# Ilumitunes-IR-String-Controller-v11.net
KiCad netlist of a schematic drawn in EAGLE
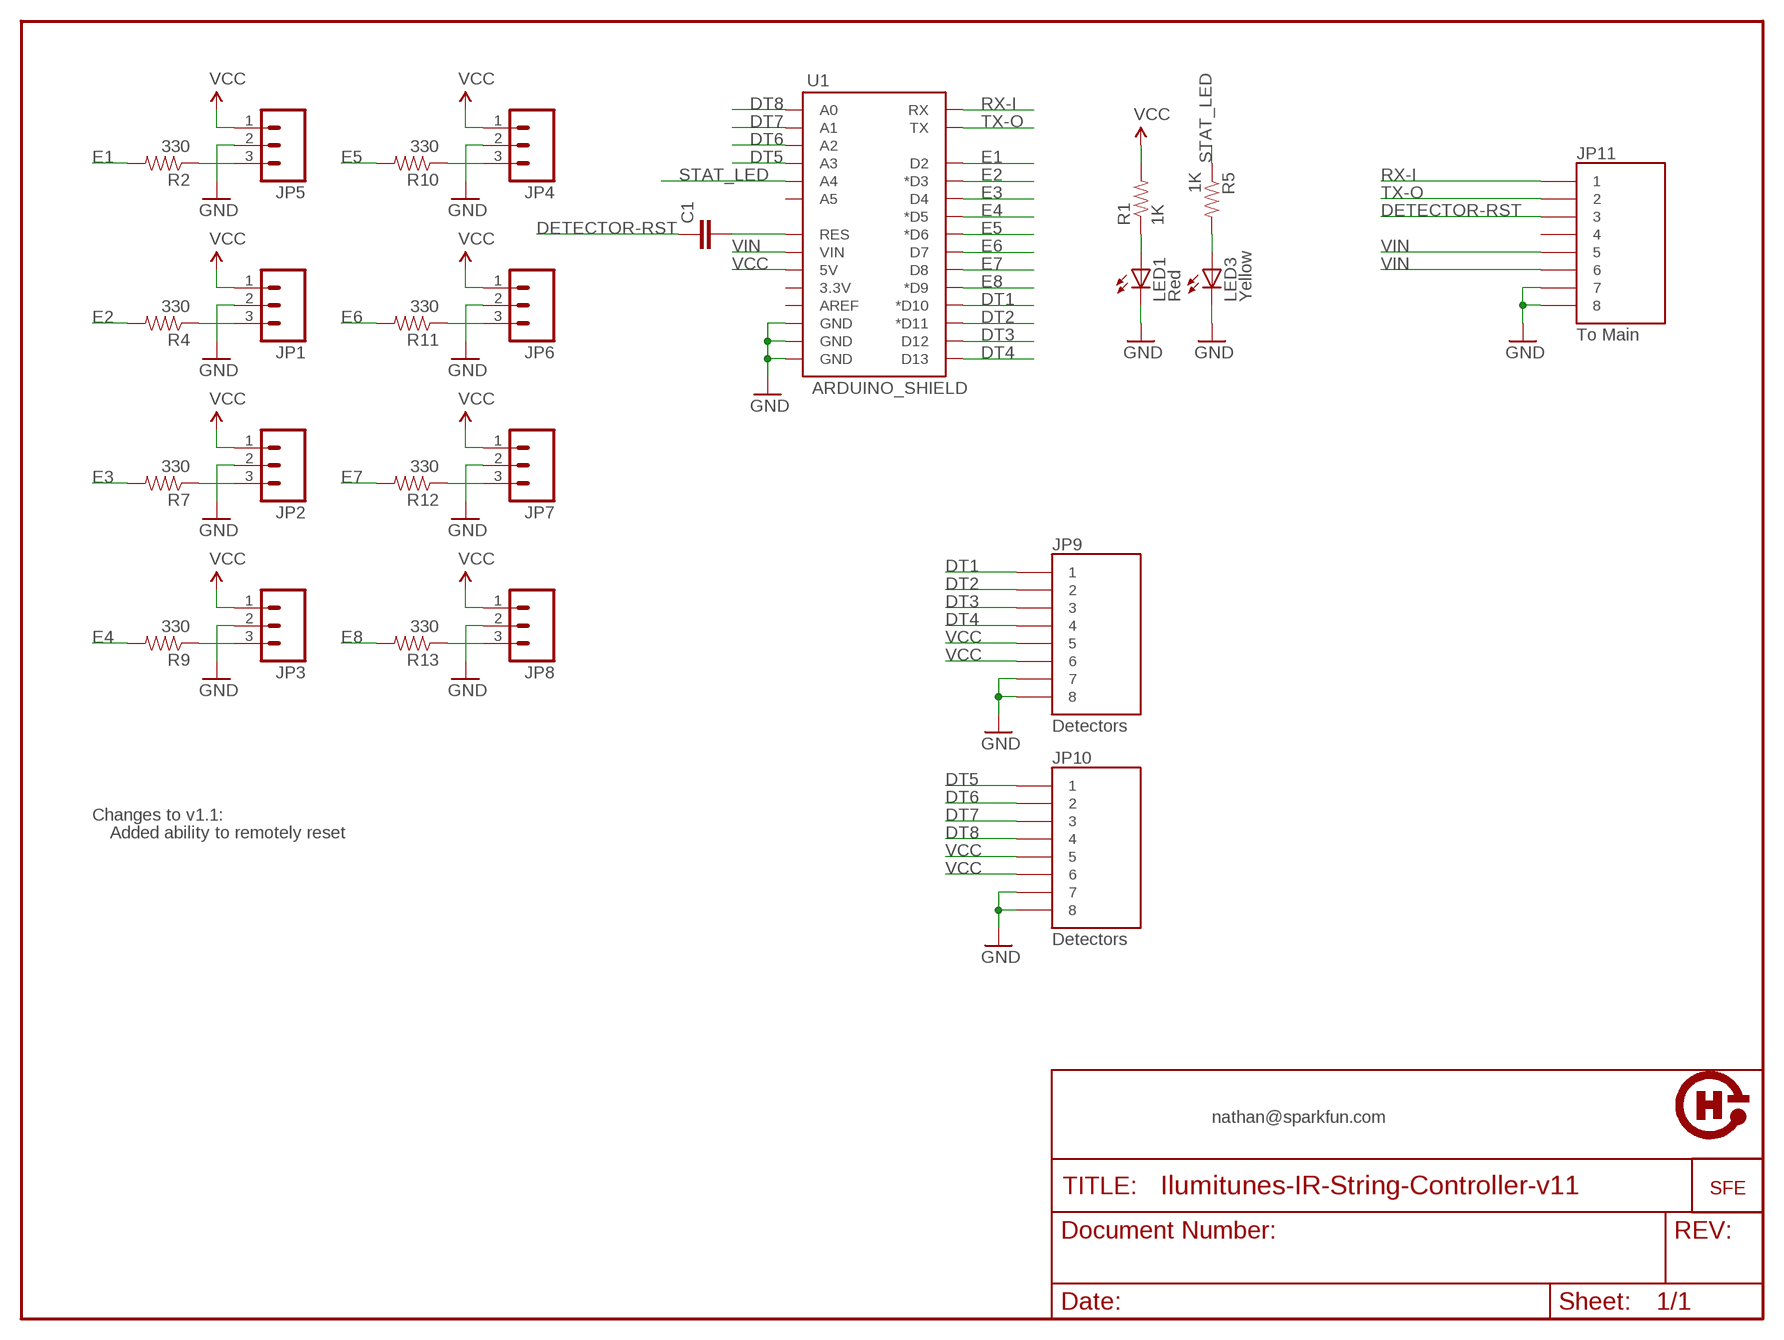
[diagram p0: schematic, sheet 1]

(export (version "E")
  (design (tool "Eeschema 10.0.6"))
  (components
    (comp (ref "C1")
      (value "CAPPTH2")
      (footprint "eagle-import:CAP-PTH-SMALL2")
      (libsource (lib "eagle-import") (part "CAPPTH2"))
    )
    (comp (ref "JP1")
      (value "M03JST-PTH-VERT")
      (footprint "eagle-import:JST-3-PTH-VERT")
      (libsource (lib "eagle-import") (part "M03JST-PTH-VERT"))
    )
    (comp (ref "JP2")
      (value "M03JST-PTH-VERT")
      (footprint "eagle-import:JST-3-PTH-VERT")
      (libsource (lib "eagle-import") (part "M03JST-PTH-VERT"))
    )
    (comp (ref "JP3")
      (value "M03JST-PTH-VERT")
      (footprint "eagle-import:JST-3-PTH-VERT")
      (libsource (lib "eagle-import") (part "M03JST-PTH-VERT"))
    )
    (comp (ref "JP4")
      (value "M03JST-PTH-VERT")
      (footprint "eagle-import:JST-3-PTH-VERT")
      (libsource (lib "eagle-import") (part "M03JST-PTH-VERT"))
    )
    (comp (ref "JP5")
      (value "M03JST-PTH-VERT")
      (footprint "eagle-import:JST-3-PTH-VERT")
      (libsource (lib "eagle-import") (part "M03JST-PTH-VERT"))
    )
    (comp (ref "JP6")
      (value "M03JST-PTH-VERT")
      (footprint "eagle-import:JST-3-PTH-VERT")
      (libsource (lib "eagle-import") (part "M03JST-PTH-VERT"))
    )
    (comp (ref "JP7")
      (value "M03JST-PTH-VERT")
      (footprint "eagle-import:JST-3-PTH-VERT")
      (libsource (lib "eagle-import") (part "M03JST-PTH-VERT"))
    )
    (comp (ref "JP8")
      (value "M03JST-PTH-VERT")
      (footprint "eagle-import:JST-3-PTH-VERT")
      (libsource (lib "eagle-import") (part "M03JST-PTH-VERT"))
    )
    (comp (ref "JP9")
      (value "Detectors")
      (footprint "eagle-import:RJ45-8")
      (libsource (lib "eagle-import") (part "RJ45-8PTH"))
    )
    (comp (ref "JP10")
      (value "Detectors")
      (footprint "eagle-import:RJ45-8")
      (libsource (lib "eagle-import") (part "RJ45-8PTH"))
    )
    (comp (ref "JP11")
      (value "To Main")
      (footprint "eagle-import:RJ45-8")
      (libsource (lib "eagle-import") (part "RJ45-8PTH"))
    )
    (comp (ref "LED1")
      (value "Red")
      (footprint "eagle-import:LED5MM")
      (libsource (lib "eagle-import") (part "LED5MM"))
    )
    (comp (ref "LED3")
      (value "Yellow")
      (footprint "eagle-import:LED5MM")
      (libsource (lib "eagle-import") (part "LED5MM"))
    )
    (comp (ref "R1")
      (value "1K")
      (footprint "eagle-import:AXIAL-0.3")
      (libsource (lib "eagle-import") (part "RESISTORAXIAL-0.3"))
    )
    (comp (ref "R2")
      (value "330")
      (footprint "eagle-import:AXIAL-0.3")
      (libsource (lib "eagle-import") (part "RESISTORAXIAL-0.3"))
    )
    (comp (ref "R4")
      (value "330")
      (footprint "eagle-import:AXIAL-0.3")
      (libsource (lib "eagle-import") (part "RESISTORAXIAL-0.3"))
    )
    (comp (ref "R5")
      (value "1K")
      (footprint "eagle-import:AXIAL-0.3")
      (libsource (lib "eagle-import") (part "RESISTORAXIAL-0.3"))
    )
    (comp (ref "R7")
      (value "330")
      (footprint "eagle-import:AXIAL-0.3")
      (libsource (lib "eagle-import") (part "RESISTORAXIAL-0.3"))
    )
    (comp (ref "R9")
      (value "330")
      (footprint "eagle-import:AXIAL-0.3")
      (libsource (lib "eagle-import") (part "RESISTORAXIAL-0.3"))
    )
    (comp (ref "R10")
      (value "330")
      (footprint "eagle-import:AXIAL-0.3")
      (libsource (lib "eagle-import") (part "RESISTORAXIAL-0.3"))
    )
    (comp (ref "R11")
      (value "330")
      (footprint "eagle-import:AXIAL-0.3")
      (libsource (lib "eagle-import") (part "RESISTORAXIAL-0.3"))
    )
    (comp (ref "R12")
      (value "330")
      (footprint "eagle-import:AXIAL-0.3")
      (libsource (lib "eagle-import") (part "RESISTORAXIAL-0.3"))
    )
    (comp (ref "R13")
      (value "330")
      (footprint "eagle-import:AXIAL-0.3")
      (libsource (lib "eagle-import") (part "RESISTORAXIAL-0.3"))
    )
    (comp (ref "U$1")
      (value "LOGO-SFENEW")
      (footprint "eagle-import:SFE-NEW-WEBLOGO")
      (libsource (lib "eagle-import") (part "LOGO-SFENEW"))
    )
    (comp (ref "U$2")
      (value "OSHW-LOGO")
      (footprint "eagle-import:OSHW-LOGO")
      (libsource (lib "eagle-import") (part "OSHW-LOGO"))
    )
    (comp (ref "U1")
      (value "ARDUINO_SHIELD")
      (footprint "eagle-import:DUEMILANOVE_SHIELD")
      (libsource (lib "eagle-import") (part "ARDUINO_SHIELDLABEL"))
    )
  )
  (nets
    (net (code "1") (name "/DETECTOR-RST") (class "Default")
      (node (ref "C1") (pin "1") (pinfunction "1_1") (pintype "passive"))
      (node (ref "JP11") (pin "3") (pinfunction "3_3") (pintype "bidirectional"))
    )
    (net (code "2") (name "/DT1") (class "Default")
      (node (ref "JP9") (pin "1") (pinfunction "1_1") (pintype "bidirectional"))
      (node (ref "U1") (pin "D10") (pinfunction "*D10_D10") (pintype "bidirectional"))
    )
    (net (code "3") (name "/DT2") (class "Default")
      (node (ref "JP9") (pin "2") (pinfunction "2_2") (pintype "bidirectional"))
      (node (ref "U1") (pin "D11") (pinfunction "*D11_D11") (pintype "bidirectional"))
    )
    (net (code "4") (name "/DT3") (class "Default")
      (node (ref "JP9") (pin "3") (pinfunction "3_3") (pintype "bidirectional"))
      (node (ref "U1") (pin "D12") (pinfunction "D12_D12") (pintype "bidirectional"))
    )
    (net (code "5") (name "/DT4") (class "Default")
      (node (ref "JP9") (pin "4") (pinfunction "4_4") (pintype "bidirectional"))
      (node (ref "U1") (pin "D13") (pinfunction "D13_D13") (pintype "bidirectional"))
    )
    (net (code "6") (name "/DT5") (class "Default")
      (node (ref "JP10") (pin "1") (pinfunction "1_1") (pintype "bidirectional"))
      (node (ref "U1") (pin "A3") (pinfunction "A3_A3") (pintype "bidirectional"))
    )
    (net (code "7") (name "/DT6") (class "Default")
      (node (ref "JP10") (pin "2") (pinfunction "2_2") (pintype "bidirectional"))
      (node (ref "U1") (pin "A2") (pinfunction "A2_A2") (pintype "bidirectional"))
    )
    (net (code "8") (name "/DT7") (class "Default")
      (node (ref "JP10") (pin "3") (pinfunction "3_3") (pintype "bidirectional"))
      (node (ref "U1") (pin "A1") (pinfunction "A1_A1") (pintype "bidirectional"))
    )
    (net (code "9") (name "/DT8") (class "Default")
      (node (ref "JP10") (pin "4") (pinfunction "4_4") (pintype "bidirectional"))
      (node (ref "U1") (pin "A0") (pinfunction "A0_A0") (pintype "bidirectional"))
    )
    (net (code "10") (name "/E1") (class "Default")
      (node (ref "R2") (pin "P$2") (pinfunction "2_P$2") (pintype "passive"))
      (node (ref "U1") (pin "D2") (pinfunction "D2_D2") (pintype "bidirectional"))
    )
    (net (code "11") (name "/E2") (class "Default")
      (node (ref "R4") (pin "P$2") (pinfunction "2_P$2") (pintype "passive"))
      (node (ref "U1") (pin "D3") (pinfunction "*D3_D3") (pintype "bidirectional"))
    )
    (net (code "12") (name "/E3") (class "Default")
      (node (ref "R7") (pin "P$2") (pinfunction "2_P$2") (pintype "passive"))
      (node (ref "U1") (pin "D4") (pinfunction "D4_D4") (pintype "bidirectional"))
    )
    (net (code "13") (name "/E4") (class "Default")
      (node (ref "R9") (pin "P$2") (pinfunction "2_P$2") (pintype "passive"))
      (node (ref "U1") (pin "D5") (pinfunction "*D5_D5") (pintype "bidirectional"))
    )
    (net (code "14") (name "/E5") (class "Default")
      (node (ref "R10") (pin "P$2") (pinfunction "2_P$2") (pintype "passive"))
      (node (ref "U1") (pin "D6") (pinfunction "*D6_D6") (pintype "bidirectional"))
    )
    (net (code "15") (name "/E6") (class "Default")
      (node (ref "R11") (pin "P$2") (pinfunction "2_P$2") (pintype "passive"))
      (node (ref "U1") (pin "D7") (pinfunction "D7_D7") (pintype "bidirectional"))
    )
    (net (code "16") (name "/E7") (class "Default")
      (node (ref "R12") (pin "P$2") (pinfunction "2_P$2") (pintype "passive"))
      (node (ref "U1") (pin "D8") (pinfunction "D8_D8") (pintype "bidirectional"))
    )
    (net (code "17") (name "/E8") (class "Default")
      (node (ref "R13") (pin "P$2") (pinfunction "2_P$2") (pintype "passive"))
      (node (ref "U1") (pin "D9") (pinfunction "*D9_D9") (pintype "bidirectional"))
    )
    (net (code "18") (name "/RX-I") (class "Default")
      (node (ref "JP11") (pin "1") (pinfunction "1_1") (pintype "bidirectional"))
      (node (ref "U1") (pin "RX") (pinfunction "RX_RX") (pintype "bidirectional"))
    )
    (net (code "19") (name "/STAT_LED") (class "Default")
      (node (ref "R5") (pin "P$1") (pinfunction "1_P$1") (pintype "passive"))
      (node (ref "U1") (pin "A4") (pinfunction "A4_A4") (pintype "bidirectional"))
    )
    (net (code "20") (name "/TX-O") (class "Default")
      (node (ref "JP11") (pin "2") (pinfunction "2_2") (pintype "bidirectional"))
      (node (ref "U1") (pin "TX") (pinfunction "TX_TX") (pintype "bidirectional"))
    )
    (net (code "21") (name "/VIN") (class "Default")
      (node (ref "JP11") (pin "5") (pinfunction "5_5") (pintype "bidirectional"))
      (node (ref "JP11") (pin "6") (pinfunction "6_6") (pintype "bidirectional"))
      (node (ref "U1") (pin "VIN") (pinfunction "VIN_VIN") (pintype "bidirectional"))
    )
    (net (code "22") (name "GND") (class "Default")
      (node (ref "JP1") (pin "2") (pinfunction "2_2") (pintype "passive"))
      (node (ref "JP10") (pin "7") (pinfunction "7_7") (pintype "bidirectional"))
      (node (ref "JP10") (pin "8") (pinfunction "8_8") (pintype "bidirectional"))
      (node (ref "JP11") (pin "7") (pinfunction "7_7") (pintype "bidirectional"))
      (node (ref "JP11") (pin "8") (pinfunction "8_8") (pintype "bidirectional"))
      (node (ref "JP2") (pin "2") (pinfunction "2_2") (pintype "passive"))
      (node (ref "JP3") (pin "2") (pinfunction "2_2") (pintype "passive"))
      (node (ref "JP4") (pin "2") (pinfunction "2_2") (pintype "passive"))
      (node (ref "JP5") (pin "2") (pinfunction "2_2") (pintype "passive"))
      (node (ref "JP6") (pin "2") (pinfunction "2_2") (pintype "passive"))
      (node (ref "JP7") (pin "2") (pinfunction "2_2") (pintype "passive"))
      (node (ref "JP8") (pin "2") (pinfunction "2_2") (pintype "passive"))
      (node (ref "JP9") (pin "7") (pinfunction "7_7") (pintype "bidirectional"))
      (node (ref "JP9") (pin "8") (pinfunction "8_8") (pintype "bidirectional"))
      (node (ref "LED1") (pin "K") (pinfunction "C_K") (pintype "passive"))
      (node (ref "LED3") (pin "K") (pinfunction "C_K") (pintype "passive"))
      (node (ref "U1") (pin "GND@0") (pinfunction "GND_GND@0") (pintype "bidirectional"))
      (node (ref "U1") (pin "GND@1") (pinfunction "GND_GND@1") (pintype "bidirectional"))
      (node (ref "U1") (pin "GND@2") (pinfunction "GND_GND@2") (pintype "bidirectional"))
    )
    (net (code "23") (name "Net-(C1-Pad2)") (class "Default")
      (node (ref "C1") (pin "2") (pinfunction "2_2") (pintype "passive"))
      (node (ref "U1") (pin "RES") (pinfunction "RES_RES") (pintype "bidirectional"))
    )
    (net (code "24") (name "Net-(R1-1)") (class "Default")
      (node (ref "LED1") (pin "A") (pinfunction "A_A") (pintype "passive"))
      (node (ref "R1") (pin "P$1") (pinfunction "1_P$1") (pintype "passive"))
    )
    (net (code "25") (name "Net-(R2-1)") (class "Default")
      (node (ref "JP5") (pin "3") (pinfunction "3_3") (pintype "passive"))
      (node (ref "R2") (pin "P$1") (pinfunction "1_P$1") (pintype "passive"))
    )
    (net (code "26") (name "Net-(R4-1)") (class "Default")
      (node (ref "JP1") (pin "3") (pinfunction "3_3") (pintype "passive"))
      (node (ref "R4") (pin "P$1") (pinfunction "1_P$1") (pintype "passive"))
    )
    (net (code "27") (name "Net-(R5-2)") (class "Default")
      (node (ref "LED3") (pin "A") (pinfunction "A_A") (pintype "passive"))
      (node (ref "R5") (pin "P$2") (pinfunction "2_P$2") (pintype "passive"))
    )
    (net (code "28") (name "Net-(R7-1)") (class "Default")
      (node (ref "JP2") (pin "3") (pinfunction "3_3") (pintype "passive"))
      (node (ref "R7") (pin "P$1") (pinfunction "1_P$1") (pintype "passive"))
    )
    (net (code "29") (name "Net-(R9-1)") (class "Default")
      (node (ref "JP3") (pin "3") (pinfunction "3_3") (pintype "passive"))
      (node (ref "R9") (pin "P$1") (pinfunction "1_P$1") (pintype "passive"))
    )
    (net (code "30") (name "Net-(R10-1)") (class "Default")
      (node (ref "JP4") (pin "3") (pinfunction "3_3") (pintype "passive"))
      (node (ref "R10") (pin "P$1") (pinfunction "1_P$1") (pintype "passive"))
    )
    (net (code "31") (name "Net-(R11-1)") (class "Default")
      (node (ref "JP6") (pin "3") (pinfunction "3_3") (pintype "passive"))
      (node (ref "R11") (pin "P$1") (pinfunction "1_P$1") (pintype "passive"))
    )
    (net (code "32") (name "Net-(R12-1)") (class "Default")
      (node (ref "JP7") (pin "3") (pinfunction "3_3") (pintype "passive"))
      (node (ref "R12") (pin "P$1") (pinfunction "1_P$1") (pintype "passive"))
    )
    (net (code "33") (name "Net-(R13-1)") (class "Default")
      (node (ref "JP8") (pin "3") (pinfunction "3_3") (pintype "passive"))
      (node (ref "R13") (pin "P$1") (pinfunction "1_P$1") (pintype "passive"))
    )
    (net (code "34") (name "VCC") (class "Default")
      (node (ref "JP1") (pin "1") (pinfunction "1_1") (pintype "passive"))
      (node (ref "JP10") (pin "5") (pinfunction "5_5") (pintype "bidirectional"))
      (node (ref "JP10") (pin "6") (pinfunction "6_6") (pintype "bidirectional"))
      (node (ref "JP2") (pin "1") (pinfunction "1_1") (pintype "passive"))
      (node (ref "JP3") (pin "1") (pinfunction "1_1") (pintype "passive"))
      (node (ref "JP4") (pin "1") (pinfunction "1_1") (pintype "passive"))
      (node (ref "JP5") (pin "1") (pinfunction "1_1") (pintype "passive"))
      (node (ref "JP6") (pin "1") (pinfunction "1_1") (pintype "passive"))
      (node (ref "JP7") (pin "1") (pinfunction "1_1") (pintype "passive"))
      (node (ref "JP8") (pin "1") (pinfunction "1_1") (pintype "passive"))
      (node (ref "JP9") (pin "5") (pinfunction "5_5") (pintype "bidirectional"))
      (node (ref "JP9") (pin "6") (pinfunction "6_6") (pintype "bidirectional"))
      (node (ref "R1") (pin "P$2") (pinfunction "2_P$2") (pintype "passive"))
      (node (ref "U1") (pin "5V") (pinfunction "5V_5V") (pintype "bidirectional"))
    )
    (net (code "35") (name "unconnected-(JP11-Pad4)") (class "Default")
      (node (ref "JP11") (pin "4") (pinfunction "4_4") (pintype "bidirectional"))
    )
    (net (code "36") (name "unconnected-(U1-Pad3.3V)") (class "Default")
      (node (ref "U1") (pin "3.3V") (pinfunction "3.3V_3.3V") (pintype "bidirectional"))
    )
    (net (code "37") (name "unconnected-(U1-PadA5)") (class "Default")
      (node (ref "U1") (pin "A5") (pinfunction "A5_A5") (pintype "bidirectional"))
    )
    (net (code "38") (name "unconnected-(U1-PadAREF)") (class "Default")
      (node (ref "U1") (pin "AREF") (pinfunction "AREF_AREF") (pintype "bidirectional"))
    )
  )
)
